# main.net
KiCad netlist of a schematic drawn in EAGLE
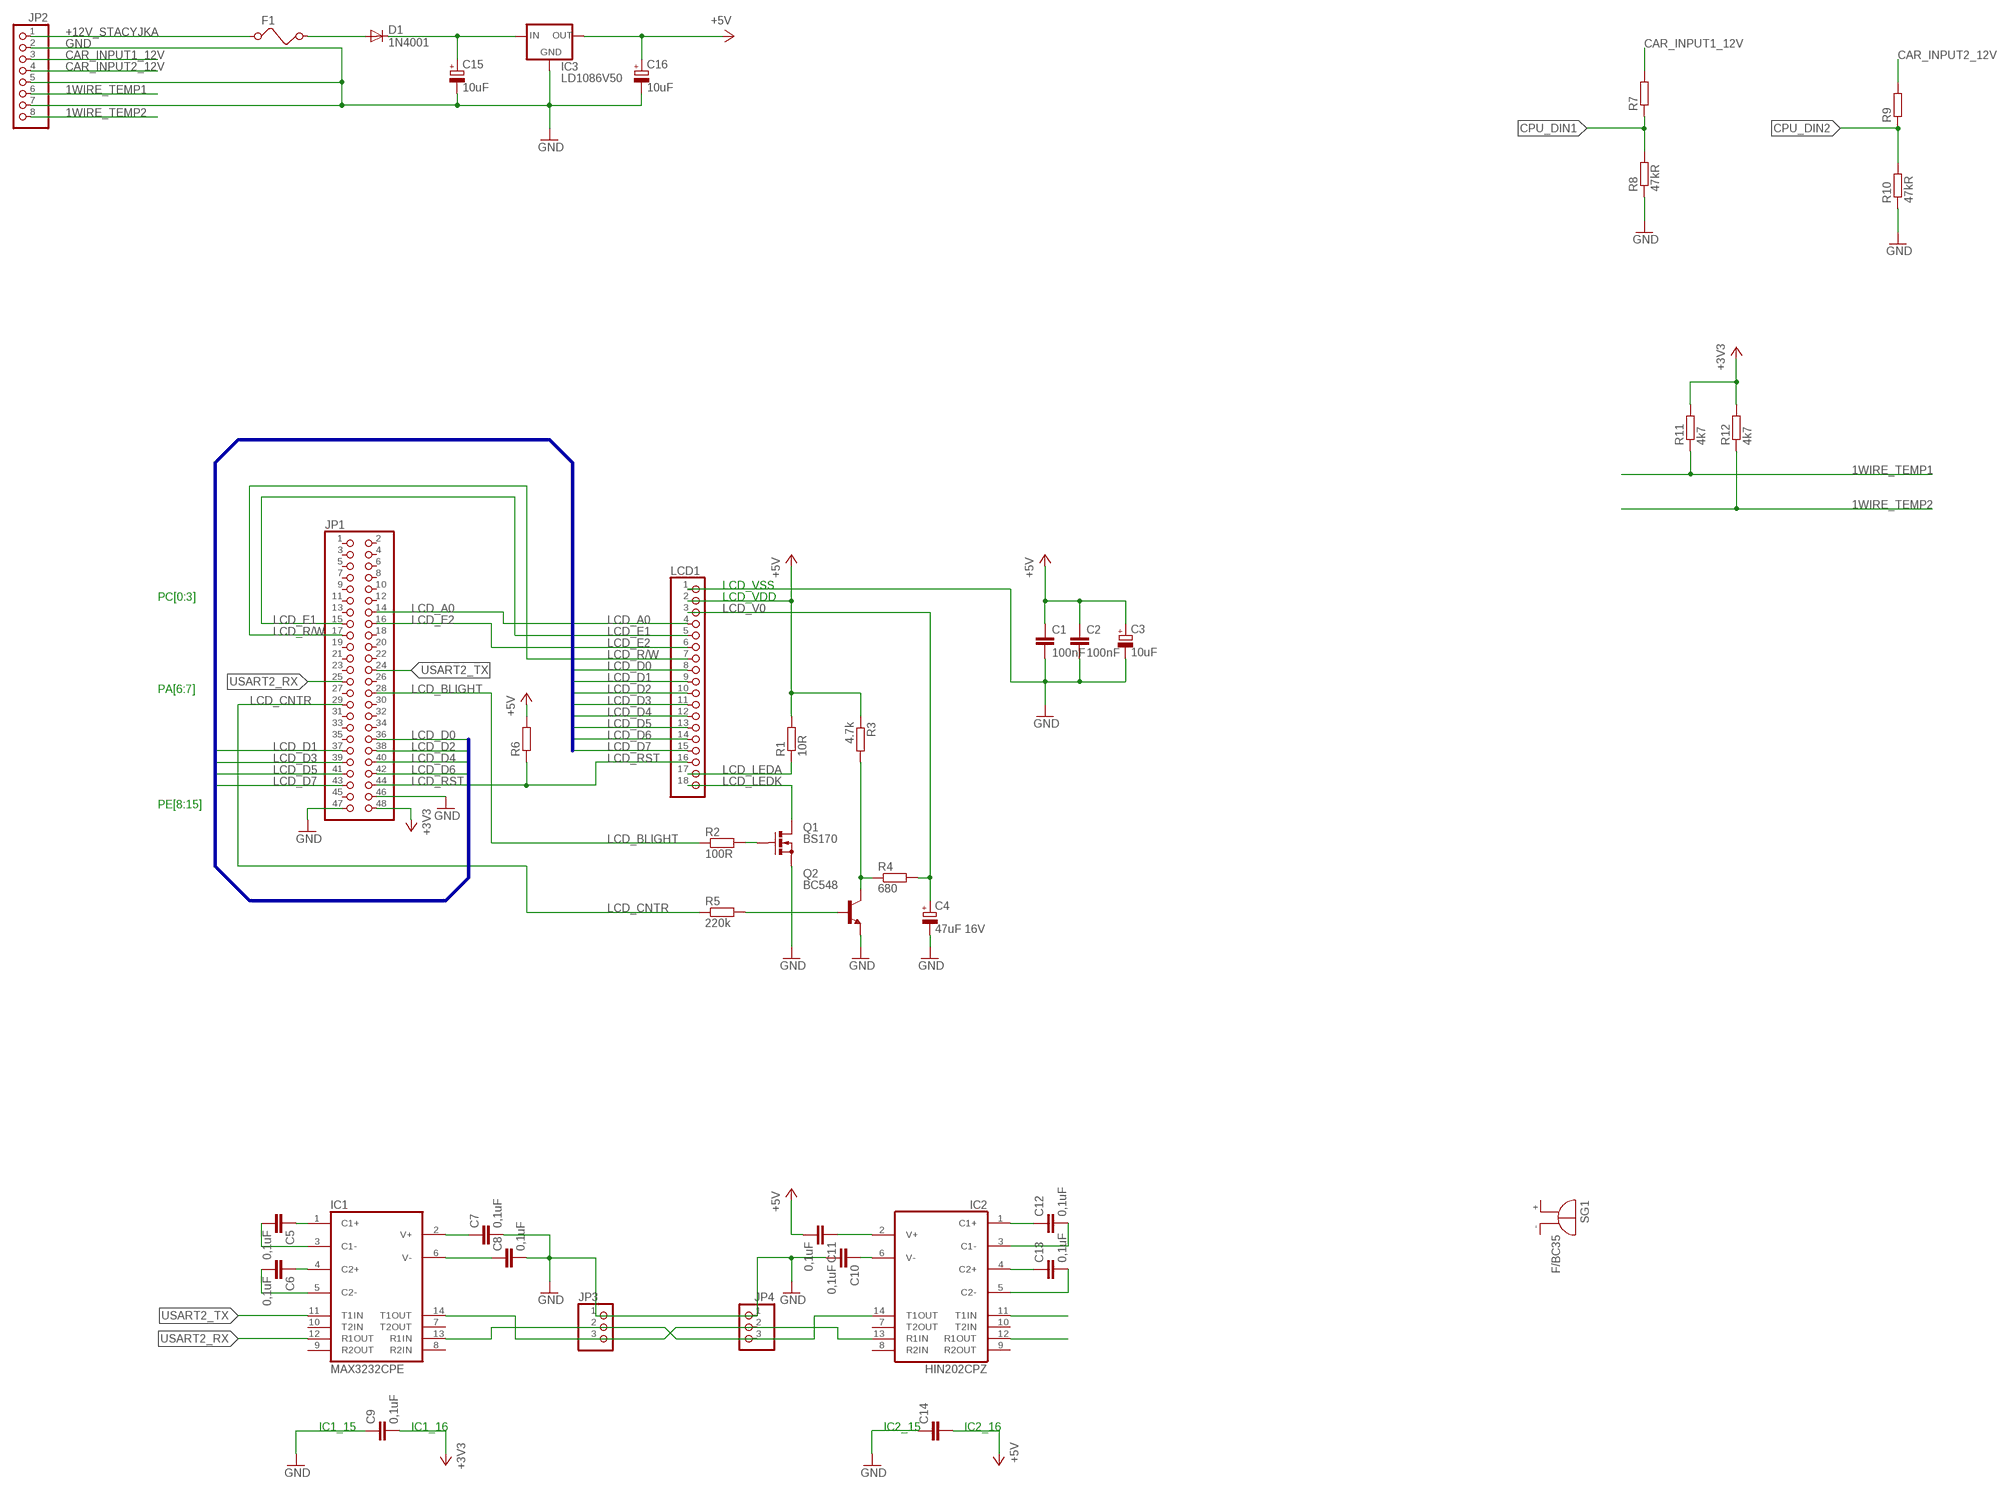
[diagram p0: schematic, sheet 1]

(export (version "E")
  (design (tool "Eeschema 10.0.6"))
  (components
    (comp (ref "C1")
      (value "100nF")
      (footprint "eagle-import:C025-024X044")
      (libsource (lib "eagle-import") (part "C-EU025-024X044"))
    )
    (comp (ref "C2")
      (value "100nF")
      (footprint "eagle-import:C025-024X044")
      (libsource (lib "eagle-import") (part "C-EU025-024X044"))
    )
    (comp (ref "C3")
      (value "10uF")
      (footprint "eagle-import:085CS_1AR")
      (libsource (lib "eagle-import") (part "CPOL-EU085CS-1AR"))
    )
    (comp (ref "C4")
      (value "47uF 16V")
      (footprint "eagle-import:085CS_1AR")
      (libsource (lib "eagle-import") (part "CPOL-EU085CS-1AR"))
    )
    (comp (ref "C5")
      (value "0,1uF")
      (footprint "eagle-import:C025-024X044")
      (libsource (lib "eagle-import") (part "C-EU025-024X044"))
    )
    (comp (ref "C6")
      (value "0,1uF")
      (footprint "eagle-import:C025-024X044")
      (libsource (lib "eagle-import") (part "C-EU025-024X044"))
    )
    (comp (ref "C7")
      (value "0,1uF")
      (footprint "eagle-import:C025-024X044")
      (libsource (lib "eagle-import") (part "C-EU025-024X044"))
    )
    (comp (ref "C8")
      (value "0,1uF")
      (footprint "eagle-import:C025-024X044")
      (libsource (lib "eagle-import") (part "C-EU025-024X044"))
    )
    (comp (ref "C9")
      (value "0,1uF")
      (footprint "eagle-import:C025-024X044")
      (libsource (lib "eagle-import") (part "C-EU025-024X044"))
    )
    (comp (ref "C10")
      (value "0,1uF")
      (footprint "eagle-import:C025-024X044")
      (libsource (lib "eagle-import") (part "C-EU025-024X044"))
    )
    (comp (ref "C11")
      (value "0,1uF")
      (footprint "eagle-import:C025-024X044")
      (libsource (lib "eagle-import") (part "C-EU025-024X044"))
    )
    (comp (ref "C12")
      (value "0,1uF")
      (footprint "eagle-import:C025-024X044")
      (libsource (lib "eagle-import") (part "C-EU025-024X044"))
    )
    (comp (ref "C13")
      (value "0,1uF")
      (footprint "eagle-import:C025-024X044")
      (libsource (lib "eagle-import") (part "C-EU025-024X044"))
    )
    (comp (ref "C14")
      (value "C-EU025-024X044")
      (footprint "eagle-import:C025-024X044")
      (libsource (lib "eagle-import") (part "C-EU025-024X044"))
    )
    (comp (ref "C15")
      (value "10uF")
      (footprint "eagle-import:085CS_1AR")
      (libsource (lib "eagle-import") (part "CPOL-EU085CS-1AR"))
    )
    (comp (ref "C16")
      (value "10uF")
      (footprint "eagle-import:085CS_1AR")
      (libsource (lib "eagle-import") (part "CPOL-EU085CS-1AR"))
    )
    (comp (ref "D1")
      (value "1N4001")
      (footprint "eagle-import:DO41-10")
      (libsource (lib "eagle-import") (part "1N4004"))
    )
    (comp (ref "F1")
      (value "FUSE")
      (footprint "eagle-import:FUSE")
      (libsource (lib "eagle-import") (part "FUSE"))
    )
    (comp (ref "IC1")
      (value "MAX3232CPE")
      (footprint "eagle-import:DIL16")
      (fields (field (name "MF") "MAXIM") (field (name "MPN") "MAX3232CPE+"))
      (libsource (lib "eagle-import") (part "MAX3232PEC"))
    )
    (comp (ref "IC2")
      (value "HIN202CPZ")
      (footprint "eagle-import:DIL16")
      (fields (field (name "MF") "MAXIM") (field (name "MPN") "MAX3232CPE+"))
      (libsource (lib "eagle-import") (part "MAX3232PEC"))
    )
    (comp (ref "IC3")
      (value "LD1086V50")
      (footprint "eagle-import:78MXXL")
      (libsource (lib "eagle-import") (part "78MXXL"))
    )
    (comp (ref "JP1")
      (value "PINHD-2X24")
      (footprint "eagle-import:2X24")
      (libsource (lib "eagle-import") (part "PINHD-2X24"))
    )
    (comp (ref "JP2")
      (value "PINHD-1X8")
      (footprint "eagle-import:1X08")
      (libsource (lib "eagle-import") (part "PINHD-1X8"))
    )
    (comp (ref "JP3")
      (value "PINHD-1X3")
      (footprint "eagle-import:1X03")
      (libsource (lib "eagle-import") (part "PINHD-1X3"))
    )
    (comp (ref "JP4")
      (value "PINHD-1X3")
      (footprint "eagle-import:1X03")
      (libsource (lib "eagle-import") (part "PINHD-1X3"))
    )
    (comp (ref "LCD1")
      (value "PINHD-1X18")
      (footprint "eagle-import:1X18")
      (libsource (lib "eagle-import") (part "PINHD-1X18"))
    )
    (comp (ref "Q1")
      (value "BS170")
      (footprint "eagle-import:SOT54E")
      (libsource (lib "eagle-import") (part "BS170"))
    )
    (comp (ref "Q2")
      (value "BC548")
      (footprint "eagle-import:TO92-EBC")
      (libsource (lib "eagle-import") (part "BC548"))
    )
    (comp (ref "R1")
      (value "10R")
      (footprint "eagle-import:0204V")
      (libsource (lib "eagle-import") (part "R-EU_0204/2V"))
    )
    (comp (ref "R2")
      (value "100R")
      (footprint "eagle-import:0204V")
      (libsource (lib "eagle-import") (part "R-EU_0204/2V"))
    )
    (comp (ref "R3")
      (value "4.7k")
      (footprint "eagle-import:0204V")
      (libsource (lib "eagle-import") (part "R-EU_0204/2V"))
    )
    (comp (ref "R4")
      (value "680")
      (footprint "eagle-import:0204V")
      (libsource (lib "eagle-import") (part "R-EU_0204/2V"))
    )
    (comp (ref "R5")
      (value "220k")
      (footprint "eagle-import:0204V")
      (libsource (lib "eagle-import") (part "R-EU_0204/2V"))
    )
    (comp (ref "R6")
      (value "R-EU_0204/2V")
      (footprint "eagle-import:0204V")
      (libsource (lib "eagle-import") (part "R-EU_0204/2V"))
    )
    (comp (ref "R7")
      (value "R-EU_0204/2V")
      (footprint "eagle-import:0204V")
      (libsource (lib "eagle-import") (part "R-EU_0204/2V"))
    )
    (comp (ref "R8")
      (value "47kR")
      (footprint "eagle-import:0204V")
      (libsource (lib "eagle-import") (part "R-EU_0204/2V"))
    )
    (comp (ref "R9")
      (value "R-EU_0204/2V")
      (footprint "eagle-import:0204V")
      (libsource (lib "eagle-import") (part "R-EU_0204/2V"))
    )
    (comp (ref "R10")
      (value "47kR")
      (footprint "eagle-import:0204V")
      (libsource (lib "eagle-import") (part "R-EU_0204/2V"))
    )
    (comp (ref "R11")
      (value "4k7")
      (footprint "eagle-import:0204V")
      (libsource (lib "eagle-import") (part "R-EU_0204/2V"))
    )
    (comp (ref "R12")
      (value "4k7")
      (footprint "eagle-import:0204V")
      (libsource (lib "eagle-import") (part "R-EU_0204/2V"))
    )
    (comp (ref "SG1")
      (value "F/BC35")
      (footprint "eagle-import:F_BC35")
      (libsource (lib "eagle-import") (part "F/BC35"))
    )
  )
  (nets
    (net (code "1") (name "+3V3") (class "Default")
      (node (ref "C9") (pin "2") (pinfunction "2_2") (pintype "passive"))
      (node (ref "JP1") (pin "48") (pinfunction "48_48") (pintype "passive"))
      (node (ref "R11") (pin "2") (pinfunction "2_2") (pintype "passive"))
      (node (ref "R12") (pin "2") (pinfunction "2_2") (pintype "passive"))
    )
    (net (code "2") (name "+5V") (class "Default")
      (node (ref "C1") (pin "1") (pinfunction "1_1") (pintype "passive"))
      (node (ref "C11") (pin "2") (pinfunction "2_2") (pintype "passive"))
      (node (ref "C14") (pin "2") (pinfunction "2_2") (pintype "passive"))
      (node (ref "C16") (pin "+") (pinfunction "+_+") (pintype "passive"))
      (node (ref "C2") (pin "1") (pinfunction "1_1") (pintype "passive"))
      (node (ref "C3") (pin "+") (pinfunction "+_+") (pintype "passive"))
      (node (ref "IC3") (pin "OUT") (pinfunction "OUT_OUT") (pintype "passive"))
      (node (ref "LCD1") (pin "2") (pinfunction "2_2") (pintype "passive"))
      (node (ref "R1") (pin "2") (pinfunction "2_2") (pintype "passive"))
      (node (ref "R3") (pin "1") (pinfunction "1_1") (pintype "passive"))
      (node (ref "R6") (pin "2") (pinfunction "2_2") (pintype "passive"))
    )
    (net (code "3") (name "/+12V_STACYJKA") (class "Default")
      (node (ref "F1") (pin "1") (pinfunction "1_1") (pintype "passive"))
      (node (ref "JP2") (pin "1") (pinfunction "1_1") (pintype "passive"))
    )
    (net (code "4") (name "/1WIRE_TEMP1") (class "Default")
      (node (ref "JP2") (pin "6") (pinfunction "6_6") (pintype "passive"))
      (node (ref "R11") (pin "1") (pinfunction "1_1") (pintype "passive"))
    )
    (net (code "5") (name "/1WIRE_TEMP2") (class "Default")
      (node (ref "JP2") (pin "8") (pinfunction "8_8") (pintype "passive"))
      (node (ref "R12") (pin "1") (pinfunction "1_1") (pintype "passive"))
    )
    (net (code "6") (name "/CAR_INPUT1_12V") (class "Default")
      (node (ref "JP2") (pin "3") (pinfunction "3_3") (pintype "passive"))
      (node (ref "R7") (pin "2") (pinfunction "2_2") (pintype "passive"))
    )
    (net (code "7") (name "/CAR_INPUT2_12V") (class "Default")
      (node (ref "JP2") (pin "4") (pinfunction "4_4") (pintype "passive"))
      (node (ref "R9") (pin "2") (pinfunction "2_2") (pintype "passive"))
    )
    (net (code "8") (name "/LCD_A0") (class "Default")
      (node (ref "JP1") (pin "14") (pinfunction "14_14") (pintype "passive"))
      (node (ref "LCD1") (pin "4") (pinfunction "4_4") (pintype "passive"))
    )
    (net (code "9") (name "/LCD_BLIGHT") (class "Default")
      (node (ref "JP1") (pin "28") (pinfunction "28_28") (pintype "passive"))
      (node (ref "R2") (pin "1") (pinfunction "1_1") (pintype "passive"))
    )
    (net (code "10") (name "/LCD_CNTR") (class "Default")
      (node (ref "JP1") (pin "29") (pinfunction "29_29") (pintype "passive"))
      (node (ref "R5") (pin "1") (pinfunction "1_1") (pintype "passive"))
    )
    (net (code "11") (name "/LCD_D0") (class "Default")
      (node (ref "JP1") (pin "36") (pinfunction "36_36") (pintype "passive"))
      (node (ref "LCD1") (pin "8") (pinfunction "8_8") (pintype "passive"))
    )
    (net (code "12") (name "/LCD_D1") (class "Default")
      (node (ref "JP1") (pin "37") (pinfunction "37_37") (pintype "passive"))
      (node (ref "LCD1") (pin "9") (pinfunction "9_9") (pintype "passive"))
    )
    (net (code "13") (name "/LCD_D2") (class "Default")
      (node (ref "JP1") (pin "38") (pinfunction "38_38") (pintype "passive"))
      (node (ref "LCD1") (pin "10") (pinfunction "10_10") (pintype "passive"))
    )
    (net (code "14") (name "/LCD_D3") (class "Default")
      (node (ref "JP1") (pin "39") (pinfunction "39_39") (pintype "passive"))
      (node (ref "LCD1") (pin "11") (pinfunction "11_11") (pintype "passive"))
    )
    (net (code "15") (name "/LCD_D4") (class "Default")
      (node (ref "JP1") (pin "40") (pinfunction "40_40") (pintype "passive"))
      (node (ref "LCD1") (pin "12") (pinfunction "12_12") (pintype "passive"))
    )
    (net (code "16") (name "/LCD_D5") (class "Default")
      (node (ref "JP1") (pin "41") (pinfunction "41_41") (pintype "passive"))
      (node (ref "LCD1") (pin "13") (pinfunction "13_13") (pintype "passive"))
    )
    (net (code "17") (name "/LCD_D6") (class "Default")
      (node (ref "JP1") (pin "42") (pinfunction "42_42") (pintype "passive"))
      (node (ref "LCD1") (pin "14") (pinfunction "14_14") (pintype "passive"))
    )
    (net (code "18") (name "/LCD_D7") (class "Default")
      (node (ref "JP1") (pin "43") (pinfunction "43_43") (pintype "passive"))
      (node (ref "LCD1") (pin "15") (pinfunction "15_15") (pintype "passive"))
    )
    (net (code "19") (name "/LCD_E1") (class "Default")
      (node (ref "JP1") (pin "15") (pinfunction "15_15") (pintype "passive"))
      (node (ref "LCD1") (pin "5") (pinfunction "5_5") (pintype "passive"))
    )
    (net (code "20") (name "/LCD_E2") (class "Default")
      (node (ref "JP1") (pin "16") (pinfunction "16_16") (pintype "passive"))
      (node (ref "LCD1") (pin "6") (pinfunction "6_6") (pintype "passive"))
    )
    (net (code "21") (name "/LCD_LEDA") (class "Default")
      (node (ref "LCD1") (pin "17") (pinfunction "17_17") (pintype "passive"))
      (node (ref "R1") (pin "1") (pinfunction "1_1") (pintype "passive"))
    )
    (net (code "22") (name "/LCD_LEDK") (class "Default")
      (node (ref "LCD1") (pin "18") (pinfunction "18_18") (pintype "passive"))
      (node (ref "Q1") (pin "D") (pinfunction "D_D") (pintype "passive"))
    )
    (net (code "23") (name "/LCD_RST") (class "Default")
      (node (ref "JP1") (pin "44") (pinfunction "44_44") (pintype "passive"))
      (node (ref "LCD1") (pin "16") (pinfunction "16_16") (pintype "passive"))
      (node (ref "R6") (pin "1") (pinfunction "1_1") (pintype "passive"))
    )
    (net (code "24") (name "/LCD_R{slash}W") (class "Default")
      (node (ref "JP1") (pin "17") (pinfunction "17_17") (pintype "passive"))
      (node (ref "LCD1") (pin "7") (pinfunction "7_7") (pintype "passive"))
    )
    (net (code "25") (name "/LCD_V0") (class "Default")
      (node (ref "C4") (pin "+") (pinfunction "+_+") (pintype "passive"))
      (node (ref "LCD1") (pin "3") (pinfunction "3_3") (pintype "passive"))
      (node (ref "R4") (pin "2") (pinfunction "2_2") (pintype "passive"))
    )
    (net (code "26") (name "CPU_DIN1") (class "Default")
      (node (ref "R7") (pin "1") (pinfunction "1_1") (pintype "passive"))
      (node (ref "R8") (pin "2") (pinfunction "2_2") (pintype "passive"))
    )
    (net (code "27") (name "CPU_DIN2") (class "Default")
      (node (ref "R10") (pin "2") (pinfunction "2_2") (pintype "passive"))
      (node (ref "R9") (pin "1") (pinfunction "1_1") (pintype "passive"))
    )
    (net (code "28") (name "GND") (class "Default")
      (node (ref "C1") (pin "2") (pinfunction "2_2") (pintype "passive"))
      (node (ref "C10") (pin "2") (pinfunction "2_2") (pintype "passive"))
      (node (ref "C14") (pin "1") (pinfunction "1_1") (pintype "passive"))
      (node (ref "C15") (pin "-") (pinfunction "-_-") (pintype "passive"))
      (node (ref "C16") (pin "-") (pinfunction "-_-") (pintype "passive"))
      (node (ref "C2") (pin "2") (pinfunction "2_2") (pintype "passive"))
      (node (ref "C3") (pin "-") (pinfunction "-_-") (pintype "passive"))
      (node (ref "C4") (pin "-") (pinfunction "-_-") (pintype "passive"))
      (node (ref "C7") (pin "2") (pinfunction "2_2") (pintype "passive"))
      (node (ref "C8") (pin "2") (pinfunction "2_2") (pintype "passive"))
      (node (ref "C9") (pin "1") (pinfunction "1_1") (pintype "passive"))
      (node (ref "IC3") (pin "GND") (pinfunction "GND_GND") (pintype "input"))
      (node (ref "JP1") (pin "46") (pinfunction "46_46") (pintype "passive"))
      (node (ref "JP1") (pin "47") (pinfunction "47_47") (pintype "passive"))
      (node (ref "JP2") (pin "2") (pinfunction "2_2") (pintype "passive"))
      (node (ref "JP2") (pin "5") (pinfunction "5_5") (pintype "passive"))
      (node (ref "JP2") (pin "7") (pinfunction "7_7") (pintype "passive"))
      (node (ref "JP3") (pin "1") (pinfunction "1_1") (pintype "passive"))
      (node (ref "JP4") (pin "1") (pinfunction "1_1") (pintype "passive"))
      (node (ref "LCD1") (pin "1") (pinfunction "1_1") (pintype "passive"))
      (node (ref "Q1") (pin "S") (pinfunction "S_S") (pintype "passive"))
      (node (ref "Q2") (pin "E") (pinfunction "E_E") (pintype "passive"))
      (node (ref "R10") (pin "1") (pinfunction "1_1") (pintype "passive"))
      (node (ref "R8") (pin "1") (pinfunction "1_1") (pintype "passive"))
    )
    (net (code "29") (name "Net-(C15-Pad+)") (class "Default")
      (node (ref "C15") (pin "+") (pinfunction "+_+") (pintype "passive"))
      (node (ref "D1") (pin "C") (pinfunction "C_C") (pintype "passive"))
      (node (ref "IC3") (pin "IN") (pinfunction "IN_IN") (pintype "input"))
    )
    (net (code "30") (name "Net-(D1-PadA)") (class "Default")
      (node (ref "D1") (pin "A") (pinfunction "A_A") (pintype "passive"))
      (node (ref "F1") (pin "2") (pinfunction "2_2") (pintype "passive"))
    )
    (net (code "31") (name "Net-(IC1A-C1+)") (class "Default")
      (node (ref "C5") (pin "1") (pinfunction "1_1") (pintype "passive"))
      (node (ref "IC1") (pin "1") (pinfunction "C1+_1") (pintype "bidirectional"))
    )
    (net (code "32") (name "Net-(IC1A-C1-)") (class "Default")
      (node (ref "C5") (pin "2") (pinfunction "2_2") (pintype "passive"))
      (node (ref "IC1") (pin "3") (pinfunction "C1-_3") (pintype "bidirectional"))
    )
    (net (code "33") (name "Net-(IC1A-C2+)") (class "Default")
      (node (ref "C6") (pin "1") (pinfunction "1_1") (pintype "passive"))
      (node (ref "IC1") (pin "4") (pinfunction "C2+_4") (pintype "bidirectional"))
    )
    (net (code "34") (name "Net-(IC1A-C2-)") (class "Default")
      (node (ref "C6") (pin "2") (pinfunction "2_2") (pintype "passive"))
      (node (ref "IC1") (pin "5") (pinfunction "C2-_5") (pintype "bidirectional"))
    )
    (net (code "35") (name "Net-(IC1A-R1IN)") (class "Default")
      (node (ref "IC1") (pin "13") (pinfunction "R1IN_13") (pintype "input"))
      (node (ref "IC2") (pin "14") (pinfunction "T1OUT_14") (pintype "output"))
      (node (ref "JP3") (pin "2") (pinfunction "2_2") (pintype "passive"))
      (node (ref "JP4") (pin "3") (pinfunction "3_3") (pintype "passive"))
    )
    (net (code "36") (name "Net-(IC1A-T1OUT)") (class "Default")
      (node (ref "IC1") (pin "14") (pinfunction "T1OUT_14") (pintype "output"))
      (node (ref "IC2") (pin "13") (pinfunction "R1IN_13") (pintype "input"))
      (node (ref "JP3") (pin "3") (pinfunction "3_3") (pintype "passive"))
      (node (ref "JP4") (pin "2") (pinfunction "2_2") (pintype "passive"))
    )
    (net (code "37") (name "Net-(IC1A-V+)") (class "Default")
      (node (ref "C7") (pin "1") (pinfunction "1_1") (pintype "passive"))
      (node (ref "IC1") (pin "2") (pinfunction "V+_2") (pintype "bidirectional"))
    )
    (net (code "38") (name "Net-(IC1A-V-)") (class "Default")
      (node (ref "C8") (pin "1") (pinfunction "1_1") (pintype "passive"))
      (node (ref "IC1") (pin "6") (pinfunction "V-_6") (pintype "bidirectional"))
    )
    (net (code "39") (name "Net-(IC2A-C1+)") (class "Default")
      (node (ref "C12") (pin "1") (pinfunction "1_1") (pintype "passive"))
      (node (ref "IC2") (pin "1") (pinfunction "C1+_1") (pintype "bidirectional"))
    )
    (net (code "40") (name "Net-(IC2A-C1-)") (class "Default")
      (node (ref "C12") (pin "2") (pinfunction "2_2") (pintype "passive"))
      (node (ref "IC2") (pin "3") (pinfunction "C1-_3") (pintype "bidirectional"))
    )
    (net (code "41") (name "Net-(IC2A-C2+)") (class "Default")
      (node (ref "C13") (pin "1") (pinfunction "1_1") (pintype "passive"))
      (node (ref "IC2") (pin "4") (pinfunction "C2+_4") (pintype "bidirectional"))
    )
    (net (code "42") (name "Net-(IC2A-C2-)") (class "Default")
      (node (ref "C13") (pin "2") (pinfunction "2_2") (pintype "passive"))
      (node (ref "IC2") (pin "5") (pinfunction "C2-_5") (pintype "bidirectional"))
    )
    (net (code "43") (name "Net-(IC2A-V+)") (class "Default")
      (node (ref "C11") (pin "1") (pinfunction "1_1") (pintype "passive"))
      (node (ref "IC2") (pin "2") (pinfunction "V+_2") (pintype "bidirectional"))
    )
    (net (code "44") (name "Net-(IC2A-V-)") (class "Default")
      (node (ref "C10") (pin "1") (pinfunction "1_1") (pintype "passive"))
      (node (ref "IC2") (pin "6") (pinfunction "V-_6") (pintype "bidirectional"))
    )
    (net (code "45") (name "Net-(Q1-PadG)") (class "Default")
      (node (ref "Q1") (pin "G") (pinfunction "G_G") (pintype "passive"))
      (node (ref "R2") (pin "2") (pinfunction "2_2") (pintype "passive"))
    )
    (net (code "46") (name "Net-(Q2-PadB)") (class "Default")
      (node (ref "Q2") (pin "B") (pinfunction "B_B") (pintype "passive"))
      (node (ref "R5") (pin "2") (pinfunction "2_2") (pintype "passive"))
    )
    (net (code "47") (name "Net-(Q2-PadC)") (class "Default")
      (node (ref "Q2") (pin "C") (pinfunction "C_C") (pintype "passive"))
      (node (ref "R3") (pin "2") (pinfunction "2_2") (pintype "passive"))
      (node (ref "R4") (pin "1") (pinfunction "1_1") (pintype "passive"))
    )
    (net (code "48") (name "USART2_RX") (class "Default")
      (node (ref "IC1") (pin "12") (pinfunction "R1OUT_12") (pintype "output"))
      (node (ref "JP1") (pin "25") (pinfunction "25_25") (pintype "passive"))
    )
    (net (code "49") (name "USART2_TX") (class "Default")
      (node (ref "IC1") (pin "11") (pinfunction "T1IN_11") (pintype "input"))
      (node (ref "JP1") (pin "24") (pinfunction "24_24") (pintype "passive"))
    )
    (net (code "50") (name "unconnected-(IC1A-R2IN-Pad8)") (class "Default")
      (node (ref "IC1") (pin "8") (pinfunction "R2IN_8") (pintype "input"))
    )
    (net (code "51") (name "unconnected-(IC1A-R2OUT-Pad9)") (class "Default")
      (node (ref "IC1") (pin "9") (pinfunction "R2OUT_9") (pintype "output"))
    )
    (net (code "52") (name "unconnected-(IC1A-T2IN-Pad10)") (class "Default")
      (node (ref "IC1") (pin "10") (pinfunction "T2IN_10") (pintype "input"))
    )
    (net (code "53") (name "unconnected-(IC1A-T2OUT-Pad7)") (class "Default")
      (node (ref "IC1") (pin "7") (pinfunction "T2OUT_7") (pintype "output"))
    )
    (net (code "54") (name "unconnected-(IC2A-R1OUT-Pad12)") (class "Default")
      (node (ref "IC2") (pin "12") (pinfunction "R1OUT_12") (pintype "output"))
    )
    (net (code "55") (name "unconnected-(IC2A-R2IN-Pad8)") (class "Default")
      (node (ref "IC2") (pin "8") (pinfunction "R2IN_8") (pintype "input"))
    )
    (net (code "56") (name "unconnected-(IC2A-R2OUT-Pad9)") (class "Default")
      (node (ref "IC2") (pin "9") (pinfunction "R2OUT_9") (pintype "output"))
    )
    (net (code "57") (name "unconnected-(IC2A-T1IN-Pad11)") (class "Default")
      (node (ref "IC2") (pin "11") (pinfunction "T1IN_11") (pintype "input"))
    )
    (net (code "58") (name "unconnected-(IC2A-T2IN-Pad10)") (class "Default")
      (node (ref "IC2") (pin "10") (pinfunction "T2IN_10") (pintype "input"))
    )
    (net (code "59") (name "unconnected-(IC2A-T2OUT-Pad7)") (class "Default")
      (node (ref "IC2") (pin "7") (pinfunction "T2OUT_7") (pintype "output"))
    )
    (net (code "60") (name "unconnected-(JP1-Pad1)") (class "Default")
      (node (ref "JP1") (pin "1") (pinfunction "1_1") (pintype "passive"))
    )
    (net (code "61") (name "unconnected-(JP1-Pad2)") (class "Default")
      (node (ref "JP1") (pin "2") (pinfunction "2_2") (pintype "passive"))
    )
    (net (code "62") (name "unconnected-(JP1-Pad3)") (class "Default")
      (node (ref "JP1") (pin "3") (pinfunction "3_3") (pintype "passive"))
    )
    (net (code "63") (name "unconnected-(JP1-Pad4)") (class "Default")
      (node (ref "JP1") (pin "4") (pinfunction "4_4") (pintype "passive"))
    )
    (net (code "64") (name "unconnected-(JP1-Pad5)") (class "Default")
      (node (ref "JP1") (pin "5") (pinfunction "5_5") (pintype "passive"))
    )
    (net (code "65") (name "unconnected-(JP1-Pad6)") (class "Default")
      (node (ref "JP1") (pin "6") (pinfunction "6_6") (pintype "passive"))
    )
    (net (code "66") (name "unconnected-(JP1-Pad7)") (class "Default")
      (node (ref "JP1") (pin "7") (pinfunction "7_7") (pintype "passive"))
    )
    (net (code "67") (name "unconnected-(JP1-Pad8)") (class "Default")
      (node (ref "JP1") (pin "8") (pinfunction "8_8") (pintype "passive"))
    )
    (net (code "68") (name "unconnected-(JP1-Pad9)") (class "Default")
      (node (ref "JP1") (pin "9") (pinfunction "9_9") (pintype "passive"))
    )
    (net (code "69") (name "unconnected-(JP1-Pad10)") (class "Default")
      (node (ref "JP1") (pin "10") (pinfunction "10_10") (pintype "passive"))
    )
    (net (code "70") (name "unconnected-(JP1-Pad11)") (class "Default")
      (node (ref "JP1") (pin "11") (pinfunction "11_11") (pintype "passive"))
    )
    (net (code "71") (name "unconnected-(JP1-Pad12)") (class "Default")
      (node (ref "JP1") (pin "12") (pinfunction "12_12") (pintype "passive"))
    )
    (net (code "72") (name "unconnected-(JP1-Pad13)") (class "Default")
      (node (ref "JP1") (pin "13") (pinfunction "13_13") (pintype "passive"))
    )
    (net (code "73") (name "unconnected-(JP1-Pad18)") (class "Default")
      (node (ref "JP1") (pin "18") (pinfunction "18_18") (pintype "passive"))
    )
    (net (code "74") (name "unconnected-(JP1-Pad19)") (class "Default")
      (node (ref "JP1") (pin "19") (pinfunction "19_19") (pintype "passive"))
    )
    (net (code "75") (name "unconnected-(JP1-Pad20)") (class "Default")
      (node (ref "JP1") (pin "20") (pinfunction "20_20") (pintype "passive"))
    )
    (net (code "76") (name "unconnected-(JP1-Pad21)") (class "Default")
      (node (ref "JP1") (pin "21") (pinfunction "21_21") (pintype "passive"))
    )
    (net (code "77") (name "unconnected-(JP1-Pad22)") (class "Default")
      (node (ref "JP1") (pin "22") (pinfunction "22_22") (pintype "passive"))
    )
    (net (code "78") (name "unconnected-(JP1-Pad23)") (class "Default")
      (node (ref "JP1") (pin "23") (pinfunction "23_23") (pintype "passive"))
    )
    (net (code "79") (name "unconnected-(JP1-Pad26)") (class "Default")
      (node (ref "JP1") (pin "26") (pinfunction "26_26") (pintype "passive"))
    )
    (net (code "80") (name "unconnected-(JP1-Pad27)") (class "Default")
      (node (ref "JP1") (pin "27") (pinfunction "27_27") (pintype "passive"))
    )
    (net (code "81") (name "unconnected-(JP1-Pad30)") (class "Default")
      (node (ref "JP1") (pin "30") (pinfunction "30_30") (pintype "passive"))
    )
    (net (code "82") (name "unconnected-(JP1-Pad31)") (class "Default")
      (node (ref "JP1") (pin "31") (pinfunction "31_31") (pintype "passive"))
    )
    (net (code "83") (name "unconnected-(JP1-Pad32)") (class "Default")
      (node (ref "JP1") (pin "32") (pinfunction "32_32") (pintype "passive"))
    )
    (net (code "84") (name "unconnected-(JP1-Pad33)") (class "Default")
      (node (ref "JP1") (pin "33") (pinfunction "33_33") (pintype "passive"))
    )
    (net (code "85") (name "unconnected-(JP1-Pad34)") (class "Default")
      (node (ref "JP1") (pin "34") (pinfunction "34_34") (pintype "passive"))
    )
    (net (code "86") (name "unconnected-(JP1-Pad35)") (class "Default")
      (node (ref "JP1") (pin "35") (pinfunction "35_35") (pintype "passive"))
    )
    (net (code "87") (name "unconnected-(JP1-Pad45)") (class "Default")
      (node (ref "JP1") (pin "45") (pinfunction "45_45") (pintype "passive"))
    )
    (net (code "88") (name "unconnected-(SG1-Pad+)") (class "Default")
      (node (ref "SG1") (pin "+") (pinfunction "+_+") (pintype "passive"))
    )
    (net (code "89") (name "unconnected-(SG1-Pad-)") (class "Default")
      (node (ref "SG1") (pin "-") (pinfunction "-_-") (pintype "passive"))
    )
  )
)
